# genPWM.net
KiCad netlist of a schematic drawn in Altium Designer
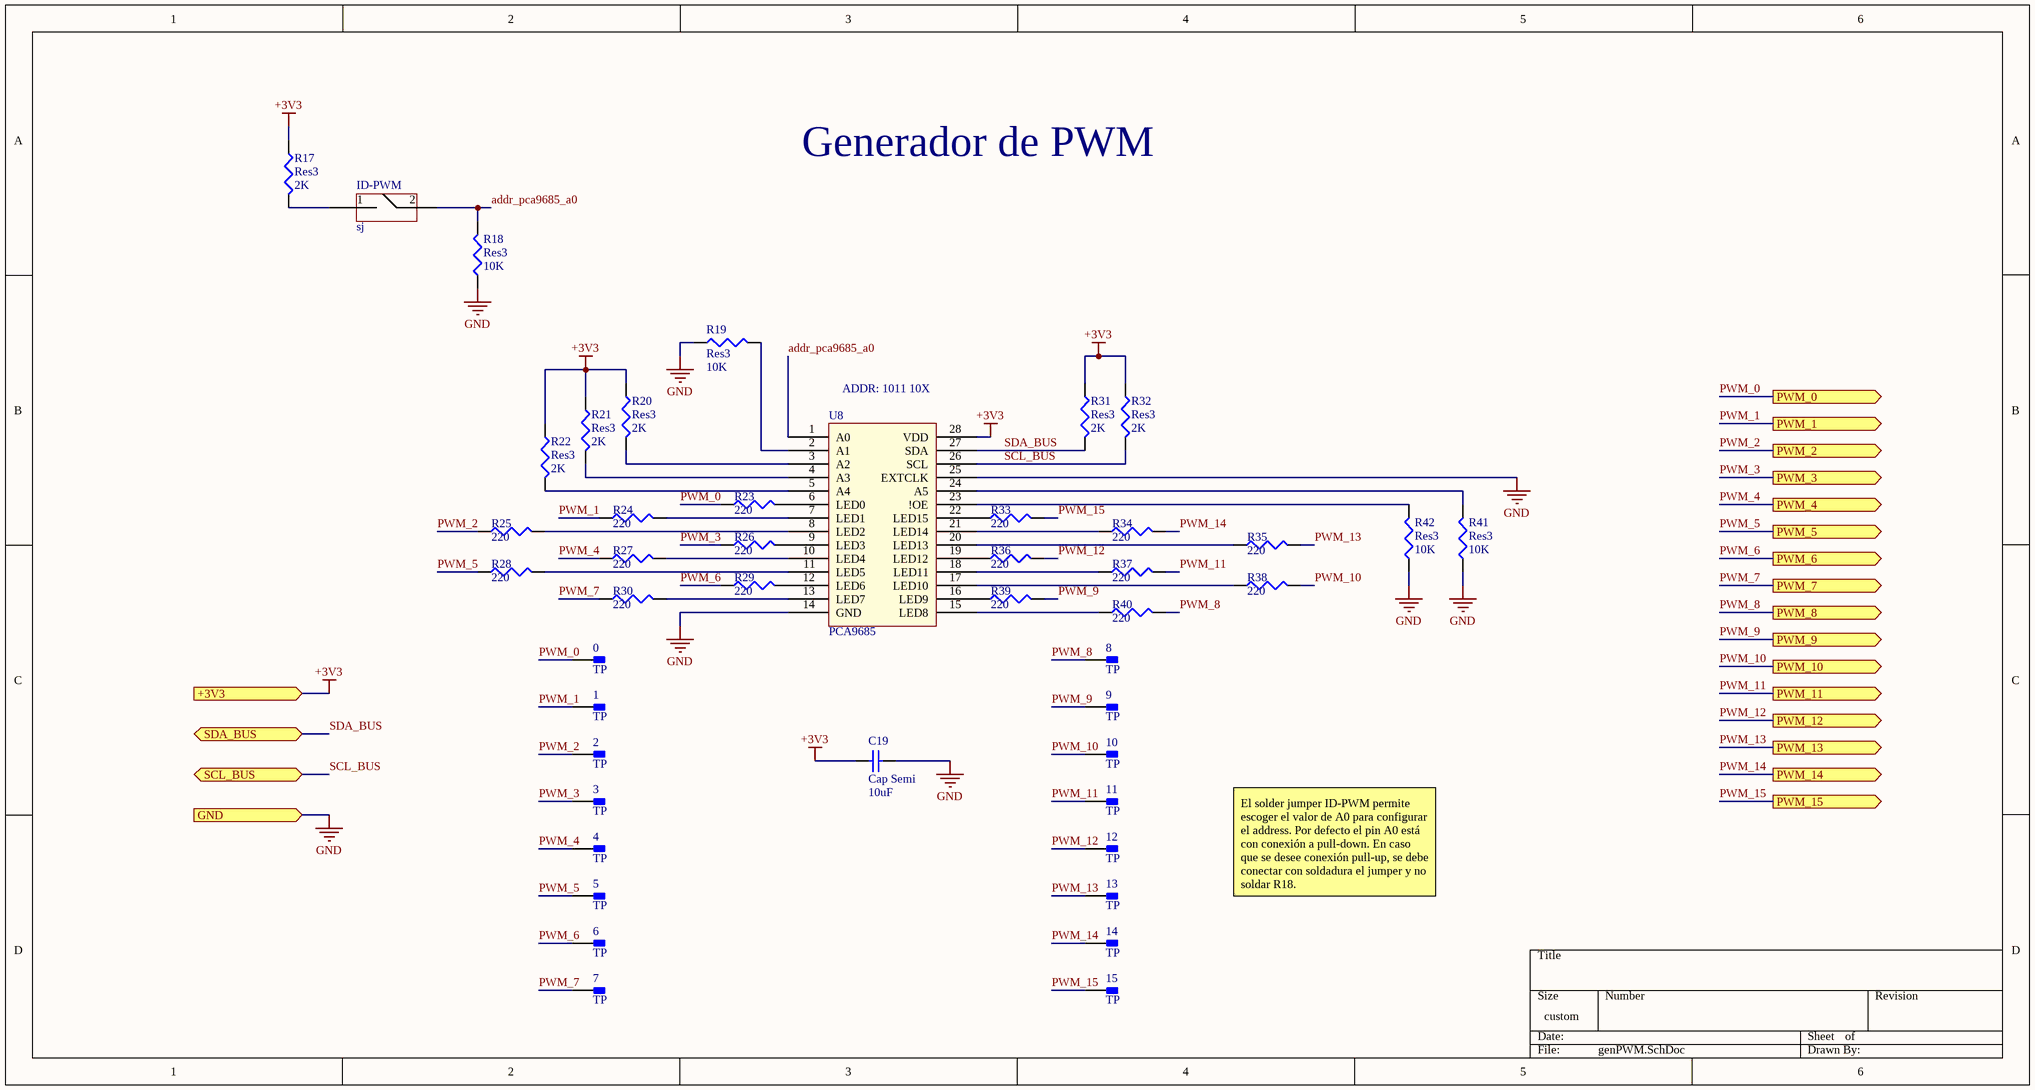
[diagram p0: genPWM.SchDoc]

(export (version "E")
  (design (tool "Eeschema 10.0.6"))
  (components
    (comp (ref "0")
      (value "TP")
      (footprint "TP")
      (description "Solder test point")
      (libsource (lib "IoWLabs") (part "TP"))
    )
    (comp (ref "1")
      (value "TP")
      (footprint "TP")
      (description "Solder test point")
      (libsource (lib "IoWLabs") (part "TP"))
    )
    (comp (ref "2")
      (value "TP")
      (footprint "TP")
      (description "Solder test point")
      (libsource (lib "IoWLabs") (part "TP"))
    )
    (comp (ref "3")
      (value "TP")
      (footprint "TP")
      (description "Solder test point")
      (libsource (lib "IoWLabs") (part "TP"))
    )
    (comp (ref "4")
      (value "TP")
      (footprint "TP")
      (description "Solder test point")
      (libsource (lib "IoWLabs") (part "TP"))
    )
    (comp (ref "5")
      (value "TP")
      (footprint "TP")
      (description "Solder test point")
      (libsource (lib "IoWLabs") (part "TP"))
    )
    (comp (ref "6")
      (value "TP")
      (footprint "TP")
      (description "Solder test point")
      (libsource (lib "IoWLabs") (part "TP"))
    )
    (comp (ref "7")
      (value "TP")
      (footprint "TP")
      (description "Solder test point")
      (libsource (lib "IoWLabs") (part "TP"))
    )
    (comp (ref "8")
      (value "TP")
      (footprint "TP")
      (description "Solder test point")
      (libsource (lib "IoWLabs") (part "TP"))
    )
    (comp (ref "9")
      (value "TP")
      (footprint "TP")
      (description "Solder test point")
      (libsource (lib "IoWLabs") (part "TP"))
    )
    (comp (ref "10")
      (value "TP")
      (footprint "TP")
      (description "Solder test point")
      (libsource (lib "IoWLabs") (part "TP"))
    )
    (comp (ref "11")
      (value "TP")
      (footprint "TP")
      (description "Solder test point")
      (libsource (lib "IoWLabs") (part "TP"))
    )
    (comp (ref "12")
      (value "TP")
      (footprint "TP")
      (description "Solder test point")
      (libsource (lib "IoWLabs") (part "TP"))
    )
    (comp (ref "13")
      (value "TP")
      (footprint "TP")
      (description "Solder test point")
      (libsource (lib "IoWLabs") (part "TP"))
    )
    (comp (ref "14")
      (value "TP")
      (footprint "TP")
      (description "Solder test point")
      (libsource (lib "IoWLabs") (part "TP"))
    )
    (comp (ref "15")
      (value "TP")
      (footprint "TP")
      (description "Solder test point")
      (libsource (lib "IoWLabs") (part "TP"))
    )
    (comp (ref "C19")
      (value "Cap Semi")
      (footprint "1608[0603]")
      (description "Capacitor (Semiconductor SIM Model)")
      (fields
        (field (name "ALTIUM_VALUE") "10uF")
        (field (name "MANUFACTURER") "Samsung Electro-Mechanics")
        (field (name "MANUFACTURER PART NUMBER") "CL10A106MQ8NNNC")
        (field (name "PUBLISHER") "Altium Limited")
      )
      (libsource (lib "Miscellaneous Devices") (part "Cap Semi"))
    )
    (comp (ref "ID-PWM")
      (value "sj")
      (footprint "SJ2")
      (description "solder jumper generic")
      (libsource (lib "IoWLabs") (part "Jumper"))
    )
    (comp (ref "R17")
      (value "Res3")
      (footprint "J1-0603")
      (description "Resistor")
      (fields
        (field (name "ALTIUM_VALUE") "2K")
        (field (name "MANUFACTURER") "YAGEO")
        (field (name "MANUFACTURER PART NUMBER") "RC0603FR-072KL")
        (field (name "PUBLISHER") "Altium Limited")
      )
      (libsource (lib "Miscellaneous Devices") (part "Res3"))
    )
    (comp (ref "R18")
      (value "Res3")
      (footprint "J1-0603")
      (description "Resistor")
      (fields
        (field (name "ALTIUM_VALUE") "10K")
        (field (name "MANUFACTURER") "PANASONIC")
        (field (name "MANUFACTURER PART NUMBER") "ERJPA3F1002V")
        (field (name "PUBLISHER") "Altium Limited")
      )
      (libsource (lib "Miscellaneous Devices") (part "Res3"))
    )
    (comp (ref "R19")
      (value "Res3")
      (footprint "J1-0603")
      (description "Resistor")
      (fields
        (field (name "ALTIUM_VALUE") "10K")
        (field (name "MANUFACTURER") "PANASONIC")
        (field (name "MANUFACTURER PART NUMBER") "ERJPA3F1002V")
        (field (name "PUBLISHER") "Altium Limited")
      )
      (libsource (lib "Miscellaneous Devices") (part "Res3"))
    )
    (comp (ref "R20")
      (value "Res3")
      (footprint "J1-0603")
      (description "Resistor")
      (fields
        (field (name "ALTIUM_VALUE") "2K")
        (field (name "MANUFACTURER") "YAGEO")
        (field (name "MANUFACTURER PART NUMBER") "RC0603FR-072KL")
        (field (name "PUBLISHER") "Altium Limited")
      )
      (libsource (lib "Miscellaneous Devices") (part "Res3"))
    )
    (comp (ref "R21")
      (value "Res3")
      (footprint "J1-0603")
      (description "Resistor")
      (fields
        (field (name "ALTIUM_VALUE") "2K")
        (field (name "MANUFACTURER") "YAGEO")
        (field (name "MANUFACTURER PART NUMBER") "RC0603FR-072KL")
        (field (name "PUBLISHER") "Altium Limited")
      )
      (libsource (lib "Miscellaneous Devices") (part "Res3"))
    )
    (comp (ref "R22")
      (value "Res3")
      (footprint "J1-0603")
      (description "Resistor")
      (fields
        (field (name "ALTIUM_VALUE") "2K")
        (field (name "MANUFACTURER") "YAGEO")
        (field (name "MANUFACTURER PART NUMBER") "RC0603FR-072KL")
        (field (name "PUBLISHER") "Altium Limited")
      )
      (libsource (lib "Miscellaneous Devices") (part "Res3"))
    )
    (comp (ref "R23")
      (value "220")
      (footprint "J1-0603")
      (description "Resistor")
      (fields
        (field (name "MANUFACTURER PART NUMBER") "RC0603FR-07220RL")
        (field (name "MANUFACTURER") "YAGEO")
        (field (name "PUBLISHER") "Altium Limited")
      )
      (libsource (lib "Miscellaneous Devices") (part "Res3"))
    )
    (comp (ref "R24")
      (value "220")
      (footprint "J1-0603")
      (description "Resistor")
      (fields
        (field (name "MANUFACTURER PART NUMBER") "RC0603FR-07220RL")
        (field (name "MANUFACTURER") "YAGEO")
        (field (name "PUBLISHER") "Altium Limited")
      )
      (libsource (lib "Miscellaneous Devices") (part "Res3"))
    )
    (comp (ref "R25")
      (value "220")
      (footprint "J1-0603")
      (description "Resistor")
      (fields
        (field (name "MANUFACTURER PART NUMBER") "RC0603FR-07220RL")
        (field (name "MANUFACTURER") "YAGEO")
        (field (name "PUBLISHER") "Altium Limited")
      )
      (libsource (lib "Miscellaneous Devices") (part "Res3"))
    )
    (comp (ref "R26")
      (value "220")
      (footprint "J1-0603")
      (description "Resistor")
      (fields
        (field (name "MANUFACTURER PART NUMBER") "RC0603FR-07220RL")
        (field (name "MANUFACTURER") "YAGEO")
        (field (name "PUBLISHER") "Altium Limited")
      )
      (libsource (lib "Miscellaneous Devices") (part "Res3"))
    )
    (comp (ref "R27")
      (value "220")
      (footprint "J1-0603")
      (description "Resistor")
      (fields
        (field (name "MANUFACTURER PART NUMBER") "RC0603FR-07220RL")
        (field (name "MANUFACTURER") "YAGEO")
        (field (name "PUBLISHER") "Altium Limited")
      )
      (libsource (lib "Miscellaneous Devices") (part "Res3"))
    )
    (comp (ref "R28")
      (value "220")
      (footprint "J1-0603")
      (description "Resistor")
      (fields
        (field (name "MANUFACTURER PART NUMBER") "RC0603FR-07220RL")
        (field (name "MANUFACTURER") "YAGEO")
        (field (name "PUBLISHER") "Altium Limited")
      )
      (libsource (lib "Miscellaneous Devices") (part "Res3"))
    )
    (comp (ref "R29")
      (value "220")
      (footprint "J1-0603")
      (description "Resistor")
      (fields
        (field (name "MANUFACTURER PART NUMBER") "RC0603FR-07220RL")
        (field (name "MANUFACTURER") "YAGEO")
        (field (name "PUBLISHER") "Altium Limited")
      )
      (libsource (lib "Miscellaneous Devices") (part "Res3"))
    )
    (comp (ref "R30")
      (value "220")
      (footprint "J1-0603")
      (description "Resistor")
      (fields
        (field (name "MANUFACTURER PART NUMBER") "RC0603FR-07220RL")
        (field (name "MANUFACTURER") "YAGEO")
        (field (name "PUBLISHER") "Altium Limited")
      )
      (libsource (lib "Miscellaneous Devices") (part "Res3"))
    )
    (comp (ref "R31")
      (value "Res3")
      (footprint "J1-0603")
      (description "Resistor")
      (fields
        (field (name "ALTIUM_VALUE") "2K")
        (field (name "MANUFACTURER") "YAGEO")
        (field (name "MANUFACTURER PART NUMBER") "RC0603FR-072KL")
        (field (name "PUBLISHER") "Altium Limited")
      )
      (libsource (lib "Miscellaneous Devices") (part "Res3"))
    )
    (comp (ref "R32")
      (value "Res3")
      (footprint "J1-0603")
      (description "Resistor")
      (fields
        (field (name "ALTIUM_VALUE") "2K")
        (field (name "MANUFACTURER") "YAGEO")
        (field (name "MANUFACTURER PART NUMBER") "RC0603FR-072KL")
        (field (name "PUBLISHER") "Altium Limited")
      )
      (libsource (lib "Miscellaneous Devices") (part "Res3"))
    )
    (comp (ref "R33")
      (value "220")
      (footprint "J1-0603")
      (description "Resistor")
      (fields
        (field (name "MANUFACTURER PART NUMBER") "RC0603FR-07220RL")
        (field (name "MANUFACTURER") "YAGEO")
        (field (name "PUBLISHER") "Altium Limited")
      )
      (libsource (lib "Miscellaneous Devices") (part "Res3"))
    )
    (comp (ref "R34")
      (value "220")
      (footprint "J1-0603")
      (description "Resistor")
      (fields
        (field (name "MANUFACTURER PART NUMBER") "RC0603FR-07220RL")
        (field (name "MANUFACTURER") "YAGEO")
        (field (name "PUBLISHER") "Altium Limited")
      )
      (libsource (lib "Miscellaneous Devices") (part "Res3"))
    )
    (comp (ref "R35")
      (value "220")
      (footprint "J1-0603")
      (description "Resistor")
      (fields
        (field (name "MANUFACTURER PART NUMBER") "RC0603FR-07220RL")
        (field (name "MANUFACTURER") "YAGEO")
        (field (name "PUBLISHER") "Altium Limited")
      )
      (libsource (lib "Miscellaneous Devices") (part "Res3"))
    )
    (comp (ref "R36")
      (value "220")
      (footprint "J1-0603")
      (description "Resistor")
      (fields
        (field (name "MANUFACTURER PART NUMBER") "RC0603FR-07220RL")
        (field (name "MANUFACTURER") "YAGEO")
        (field (name "PUBLISHER") "Altium Limited")
      )
      (libsource (lib "Miscellaneous Devices") (part "Res3"))
    )
    (comp (ref "R37")
      (value "220")
      (footprint "J1-0603")
      (description "Resistor")
      (fields
        (field (name "MANUFACTURER PART NUMBER") "RC0603FR-07220RL")
        (field (name "MANUFACTURER") "YAGEO")
        (field (name "PUBLISHER") "Altium Limited")
      )
      (libsource (lib "Miscellaneous Devices") (part "Res3"))
    )
    (comp (ref "R38")
      (value "220")
      (footprint "J1-0603")
      (description "Resistor")
      (fields
        (field (name "MANUFACTURER PART NUMBER") "RC0603FR-07220RL")
        (field (name "MANUFACTURER") "YAGEO")
        (field (name "PUBLISHER") "Altium Limited")
      )
      (libsource (lib "Miscellaneous Devices") (part "Res3"))
    )
    (comp (ref "R39")
      (value "220")
      (footprint "J1-0603")
      (description "Resistor")
      (fields
        (field (name "MANUFACTURER PART NUMBER") "RC0603FR-07220RL")
        (field (name "MANUFACTURER") "YAGEO")
        (field (name "PUBLISHER") "Altium Limited")
      )
      (libsource (lib "Miscellaneous Devices") (part "Res3"))
    )
    (comp (ref "R40")
      (value "220")
      (footprint "J1-0603")
      (description "Resistor")
      (fields
        (field (name "MANUFACTURER PART NUMBER") "RC0603FR-07220RL")
        (field (name "MANUFACTURER") "YAGEO")
        (field (name "PUBLISHER") "Altium Limited")
      )
      (libsource (lib "Miscellaneous Devices") (part "Res3"))
    )
    (comp (ref "R41")
      (value "Res3")
      (footprint "J1-0603")
      (description "Resistor")
      (fields
        (field (name "ALTIUM_VALUE") "10K")
        (field (name "MANUFACTURER") "PANASONIC")
        (field (name "MANUFACTURER PART NUMBER") "ERJPA3F1002V")
        (field (name "PUBLISHER") "Altium Limited")
      )
      (libsource (lib "Miscellaneous Devices") (part "Res3"))
    )
    (comp (ref "R42")
      (value "Res3")
      (footprint "J1-0603")
      (description "Resistor")
      (fields
        (field (name "ALTIUM_VALUE") "10K")
        (field (name "MANUFACTURER") "PANASONIC")
        (field (name "MANUFACTURER PART NUMBER") "ERJPA3F1002V")
        (field (name "PUBLISHER") "Altium Limited")
      )
      (libsource (lib "Miscellaneous Devices") (part "Res3"))
    )
    (comp (ref "U8")
      (value "PCA9685")
      (footprint "SSOP-28_L")
      (description "LED Drivers,16CH, I2C, TSSOP-28")
      (fields
        (field (name "MANUFACTURER") "NXP Semicon")
        (field (name "MANUFACTURER PART NUMBER") "PCA9685PW/Q900,118")
      )
      (libsource (lib "IoWLabs") (part "PCA9685"))
    )
  )
  (nets
    (net (code "1") (name "+3V3") (class "Default")
      (node (ref "C19") (pin "2") (pinfunction "2_2") (pintype "passive"))
      (node (ref "R17") (pin "1") (pinfunction "1_1") (pintype "passive"))
      (node (ref "R20") (pin "1") (pinfunction "1_1") (pintype "passive"))
      (node (ref "R21") (pin "1") (pinfunction "1_1") (pintype "passive"))
      (node (ref "R22") (pin "1") (pinfunction "1_1") (pintype "passive"))
      (node (ref "R31") (pin "1") (pinfunction "1_1") (pintype "passive"))
      (node (ref "R32") (pin "1") (pinfunction "1_1") (pintype "passive"))
      (node (ref "U8") (pin "28") (pinfunction "VDD_28") (pintype "passive"))
    )
    (net (code "2") (name "/PWM_0") (class "Default")
      (node (ref "0") (pin "1") (pinfunction "1_1") (pintype "passive"))
      (node (ref "R23") (pin "1") (pinfunction "1_1") (pintype "passive"))
    )
    (net (code "3") (name "/PWM_1") (class "Default")
      (node (ref "1") (pin "1") (pinfunction "1_1") (pintype "passive"))
      (node (ref "R24") (pin "1") (pinfunction "1_1") (pintype "passive"))
    )
    (net (code "4") (name "/PWM_2") (class "Default")
      (node (ref "2") (pin "1") (pinfunction "1_1") (pintype "passive"))
      (node (ref "R25") (pin "1") (pinfunction "1_1") (pintype "passive"))
    )
    (net (code "5") (name "/PWM_3") (class "Default")
      (node (ref "3") (pin "1") (pinfunction "1_1") (pintype "passive"))
      (node (ref "R26") (pin "1") (pinfunction "1_1") (pintype "passive"))
    )
    (net (code "6") (name "/PWM_4") (class "Default")
      (node (ref "4") (pin "1") (pinfunction "1_1") (pintype "passive"))
      (node (ref "R27") (pin "1") (pinfunction "1_1") (pintype "passive"))
    )
    (net (code "7") (name "/PWM_5") (class "Default")
      (node (ref "5") (pin "1") (pinfunction "1_1") (pintype "passive"))
      (node (ref "R28") (pin "1") (pinfunction "1_1") (pintype "passive"))
    )
    (net (code "8") (name "/PWM_6") (class "Default")
      (node (ref "6") (pin "1") (pinfunction "1_1") (pintype "passive"))
      (node (ref "R29") (pin "1") (pinfunction "1_1") (pintype "passive"))
    )
    (net (code "9") (name "/PWM_7") (class "Default")
      (node (ref "7") (pin "1") (pinfunction "1_1") (pintype "passive"))
      (node (ref "R30") (pin "1") (pinfunction "1_1") (pintype "passive"))
    )
    (net (code "10") (name "/PWM_8") (class "Default")
      (node (ref "8") (pin "1") (pinfunction "1_1") (pintype "passive"))
      (node (ref "R40") (pin "2") (pinfunction "2_2") (pintype "passive"))
    )
    (net (code "11") (name "/PWM_9") (class "Default")
      (node (ref "9") (pin "1") (pinfunction "1_1") (pintype "passive"))
      (node (ref "R39") (pin "2") (pinfunction "2_2") (pintype "passive"))
    )
    (net (code "12") (name "/PWM_10") (class "Default")
      (node (ref "10") (pin "1") (pinfunction "1_1") (pintype "passive"))
      (node (ref "R38") (pin "2") (pinfunction "2_2") (pintype "passive"))
    )
    (net (code "13") (name "/PWM_11") (class "Default")
      (node (ref "11") (pin "1") (pinfunction "1_1") (pintype "passive"))
      (node (ref "R37") (pin "2") (pinfunction "2_2") (pintype "passive"))
    )
    (net (code "14") (name "/PWM_12") (class "Default")
      (node (ref "12") (pin "1") (pinfunction "1_1") (pintype "passive"))
      (node (ref "R36") (pin "2") (pinfunction "2_2") (pintype "passive"))
    )
    (net (code "15") (name "/PWM_13") (class "Default")
      (node (ref "13") (pin "1") (pinfunction "1_1") (pintype "passive"))
      (node (ref "R35") (pin "2") (pinfunction "2_2") (pintype "passive"))
    )
    (net (code "16") (name "/PWM_14") (class "Default")
      (node (ref "14") (pin "1") (pinfunction "1_1") (pintype "passive"))
      (node (ref "R34") (pin "2") (pinfunction "2_2") (pintype "passive"))
    )
    (net (code "17") (name "/PWM_15") (class "Default")
      (node (ref "15") (pin "1") (pinfunction "1_1") (pintype "passive"))
      (node (ref "R33") (pin "2") (pinfunction "2_2") (pintype "passive"))
    )
    (net (code "18") (name "/SCL_BUS") (class "Default")
      (node (ref "R32") (pin "2") (pinfunction "2_2") (pintype "passive"))
      (node (ref "U8") (pin "26") (pinfunction "SCL_26") (pintype "passive"))
    )
    (net (code "19") (name "/SDA_BUS") (class "Default")
      (node (ref "R31") (pin "2") (pinfunction "2_2") (pintype "passive"))
      (node (ref "U8") (pin "27") (pinfunction "SDA_27") (pintype "passive"))
    )
    (net (code "20") (name "/addr_pca9685_a0") (class "Default")
      (node (ref "ID-PWM") (pin "2") (pinfunction "2_2") (pintype "passive"))
      (node (ref "R18") (pin "2") (pinfunction "2_2") (pintype "passive"))
      (node (ref "U8") (pin "1") (pinfunction "A0_1") (pintype "passive"))
    )
    (net (code "21") (name "GND") (class "Default")
      (node (ref "C19") (pin "1") (pinfunction "1_1") (pintype "passive"))
      (node (ref "R18") (pin "1") (pinfunction "1_1") (pintype "passive"))
      (node (ref "R19") (pin "1") (pinfunction "1_1") (pintype "passive"))
      (node (ref "R41") (pin "1") (pinfunction "1_1") (pintype "passive"))
      (node (ref "R42") (pin "1") (pinfunction "1_1") (pintype "passive"))
      (node (ref "U8") (pin "14") (pinfunction "GND_14") (pintype "passive"))
      (node (ref "U8") (pin "25") (pinfunction "EXTCLK_25") (pintype "passive"))
    )
    (net (code "22") (name "Net-(ID-PWM-Pad1)") (class "Default")
      (node (ref "ID-PWM") (pin "1") (pinfunction "1_1") (pintype "passive"))
      (node (ref "R17") (pin "2") (pinfunction "2_2") (pintype "passive"))
    )
    (net (code "23") (name "Net-(U8-!OE)") (class "Default")
      (node (ref "R42") (pin "2") (pinfunction "2_2") (pintype "passive"))
      (node (ref "U8") (pin "23") (pinfunction "!OE_23") (pintype "passive"))
    )
    (net (code "24") (name "Net-(U8-A1)") (class "Default")
      (node (ref "R19") (pin "2") (pinfunction "2_2") (pintype "passive"))
      (node (ref "U8") (pin "2") (pinfunction "A1_2") (pintype "passive"))
    )
    (net (code "25") (name "Net-(U8-A2)") (class "Default")
      (node (ref "R20") (pin "2") (pinfunction "2_2") (pintype "passive"))
      (node (ref "U8") (pin "3") (pinfunction "A2_3") (pintype "passive"))
    )
    (net (code "26") (name "Net-(U8-A3)") (class "Default")
      (node (ref "R21") (pin "2") (pinfunction "2_2") (pintype "passive"))
      (node (ref "U8") (pin "4") (pinfunction "A3_4") (pintype "passive"))
    )
    (net (code "27") (name "Net-(U8-A4)") (class "Default")
      (node (ref "R22") (pin "2") (pinfunction "2_2") (pintype "passive"))
      (node (ref "U8") (pin "5") (pinfunction "A4_5") (pintype "passive"))
    )
    (net (code "28") (name "Net-(U8-A5)") (class "Default")
      (node (ref "R41") (pin "2") (pinfunction "2_2") (pintype "passive"))
      (node (ref "U8") (pin "24") (pinfunction "A5_24") (pintype "passive"))
    )
    (net (code "29") (name "Net-(U8-LED0)") (class "Default")
      (node (ref "R23") (pin "2") (pinfunction "2_2") (pintype "passive"))
      (node (ref "U8") (pin "6") (pinfunction "LED0_6") (pintype "passive"))
    )
    (net (code "30") (name "Net-(U8-LED1)") (class "Default")
      (node (ref "R24") (pin "2") (pinfunction "2_2") (pintype "passive"))
      (node (ref "U8") (pin "7") (pinfunction "LED1_7") (pintype "passive"))
    )
    (net (code "31") (name "Net-(U8-LED2)") (class "Default")
      (node (ref "R25") (pin "2") (pinfunction "2_2") (pintype "passive"))
      (node (ref "U8") (pin "8") (pinfunction "LED2_8") (pintype "passive"))
    )
    (net (code "32") (name "Net-(U8-LED3)") (class "Default")
      (node (ref "R26") (pin "2") (pinfunction "2_2") (pintype "passive"))
      (node (ref "U8") (pin "9") (pinfunction "LED3_9") (pintype "passive"))
    )
    (net (code "33") (name "Net-(U8-LED4)") (class "Default")
      (node (ref "R27") (pin "2") (pinfunction "2_2") (pintype "passive"))
      (node (ref "U8") (pin "10") (pinfunction "LED4_10") (pintype "passive"))
    )
    (net (code "34") (name "Net-(U8-LED5)") (class "Default")
      (node (ref "R28") (pin "2") (pinfunction "2_2") (pintype "passive"))
      (node (ref "U8") (pin "11") (pinfunction "LED5_11") (pintype "passive"))
    )
    (net (code "35") (name "Net-(U8-LED6)") (class "Default")
      (node (ref "R29") (pin "2") (pinfunction "2_2") (pintype "passive"))
      (node (ref "U8") (pin "12") (pinfunction "LED6_12") (pintype "passive"))
    )
    (net (code "36") (name "Net-(U8-LED7)") (class "Default")
      (node (ref "R30") (pin "2") (pinfunction "2_2") (pintype "passive"))
      (node (ref "U8") (pin "13") (pinfunction "LED7_13") (pintype "passive"))
    )
    (net (code "37") (name "Net-(U8-LED8)") (class "Default")
      (node (ref "R40") (pin "1") (pinfunction "1_1") (pintype "passive"))
      (node (ref "U8") (pin "15") (pinfunction "LED8_15") (pintype "passive"))
    )
    (net (code "38") (name "Net-(U8-LED9)") (class "Default")
      (node (ref "R39") (pin "1") (pinfunction "1_1") (pintype "passive"))
      (node (ref "U8") (pin "16") (pinfunction "LED9_16") (pintype "passive"))
    )
    (net (code "39") (name "Net-(U8-LED10)") (class "Default")
      (node (ref "R38") (pin "1") (pinfunction "1_1") (pintype "passive"))
      (node (ref "U8") (pin "17") (pinfunction "LED10_17") (pintype "passive"))
    )
    (net (code "40") (name "Net-(U8-LED11)") (class "Default")
      (node (ref "R37") (pin "1") (pinfunction "1_1") (pintype "passive"))
      (node (ref "U8") (pin "18") (pinfunction "LED11_18") (pintype "passive"))
    )
    (net (code "41") (name "Net-(U8-LED12)") (class "Default")
      (node (ref "R36") (pin "1") (pinfunction "1_1") (pintype "passive"))
      (node (ref "U8") (pin "19") (pinfunction "LED12_19") (pintype "passive"))
    )
    (net (code "42") (name "Net-(U8-LED13)") (class "Default")
      (node (ref "R35") (pin "1") (pinfunction "1_1") (pintype "passive"))
      (node (ref "U8") (pin "20") (pinfunction "LED13_20") (pintype "passive"))
    )
    (net (code "43") (name "Net-(U8-LED14)") (class "Default")
      (node (ref "R34") (pin "1") (pinfunction "1_1") (pintype "passive"))
      (node (ref "U8") (pin "21") (pinfunction "LED14_21") (pintype "passive"))
    )
    (net (code "44") (name "Net-(U8-LED15)") (class "Default")
      (node (ref "R33") (pin "1") (pinfunction "1_1") (pintype "passive"))
      (node (ref "U8") (pin "22") (pinfunction "LED15_22") (pintype "passive"))
    )
  )
)
